# MCU_64.net
KiCad netlist of a schematic drawn in Altium Designer
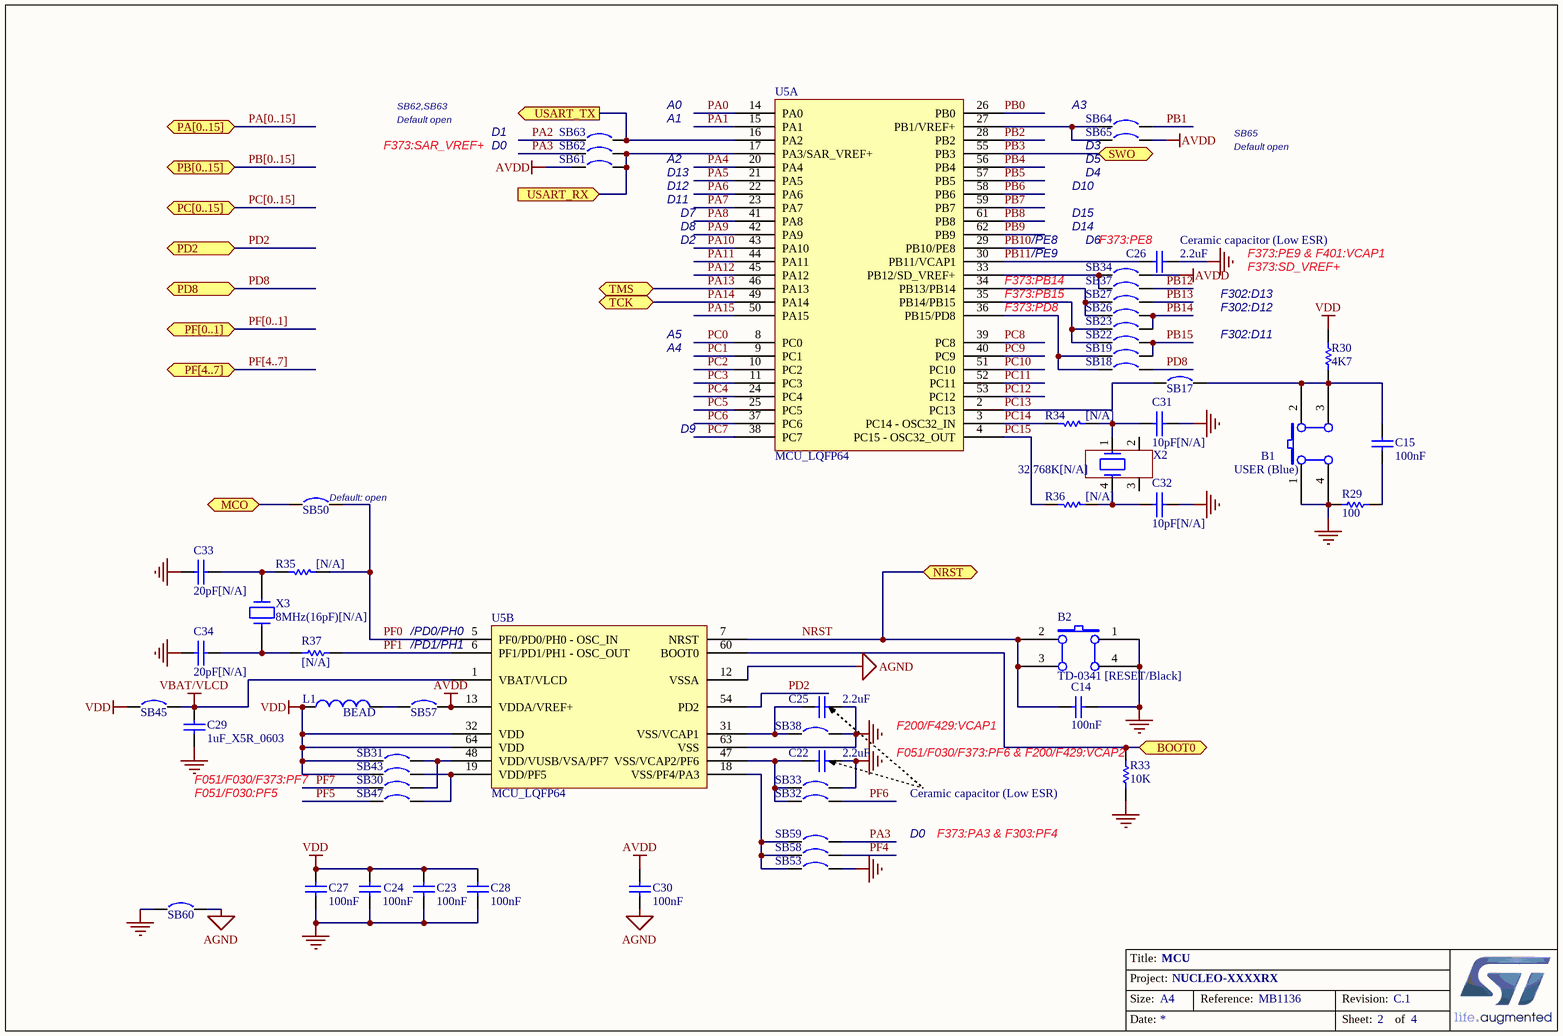
[diagram p0: MCU_64.SchDoc]

(export (version "E")
  (design (tool "Eeschema 10.0.6"))
  (components
    (comp (ref "B1")
      (value "USER (Blue)")
      (footprint "PB10")
      (description "SE PUSHBUTTON")
      (libsource (lib "Documents") (part "SW PUSHBUTTON"))
    )
    (comp (ref "B2")
      (value "TD-0341 [RESET/Black]")
      (footprint "PB10")
      (description "SE PUSHBUTTON")
      (libsource (lib "Documents") (part "SW PUSHBUTTON"))
    )
    (comp (ref "C14")
      (value "100nF")
      (footprint "0603C")
      (description "Capacitor")
      (fields (field (name "PUBLISHER") "Altium Limited"))
      (libsource (lib "Miscellaneous Devices") (part "CAP"))
    )
    (comp (ref "C15")
      (value "100nF")
      (footprint "0603C")
      (description "Capacitor")
      (fields (field (name "PUBLISHER") "Altium Limited"))
      (libsource (lib "Miscellaneous Devices") (part "CAP"))
    )
    (comp (ref "C22")
      (value "2.2uF")
      (footprint "TAN-A")
      (description "Capacitor,2.2uF,16V, X7R,10%,0805,YAGEO")
      (libsource (lib "MCD_TOOLS") (part "Cap_2.2uF_X7R_10%_0805"))
    )
    (comp (ref "C23")
      (value "100nF")
      (footprint "0603C")
      (description "Capacitor")
      (fields (field (name "PUBLISHER") "Altium Limited"))
      (libsource (lib "Miscellaneous Devices") (part "Cap"))
    )
    (comp (ref "C24")
      (value "100nF")
      (footprint "0603C")
      (description "Capacitor")
      (fields (field (name "PUBLISHER") "Altium Limited"))
      (libsource (lib "Miscellaneous Devices") (part "Cap"))
    )
    (comp (ref "C25")
      (value "2.2uF")
      (footprint "TAN-A")
      (description "Capacitor,2.2uF,16V, X7R,10%,0805,YAGEO")
      (libsource (lib "MCD_TOOLS") (part "Cap_2.2uF_X7R_10%_0805"))
    )
    (comp (ref "C26")
      (value "2.2uF")
      (footprint "TAN-A")
      (description "Capacitor,2.2uF,16V, X7R,10%,0805,YAGEO")
      (libsource (lib "MCD_TOOLS") (part "Cap_2.2uF_X7R_10%_0805"))
    )
    (comp (ref "C27")
      (value "100nF")
      (footprint "0603C")
      (description "Capacitor")
      (fields (field (name "PUBLISHER") "Altium Limited"))
      (libsource (lib "Miscellaneous Devices") (part "Cap"))
    )
    (comp (ref "C28")
      (value "100nF")
      (footprint "0603C")
      (description "Capacitor")
      (fields (field (name "PUBLISHER") "Altium Limited"))
      (libsource (lib "Miscellaneous Devices") (part "Cap"))
    )
    (comp (ref "C29")
      (value "1uF_X5R_0603")
      (footprint "0603C")
      (description "0603  X5R 1µF")
      (fields (field (name "TOLERANCE") "10%"))
      (libsource (lib "MB963_1") (part "CAP SMD 0603  X5R 1µF 25V 10%"))
    )
    (comp (ref "C30")
      (value "100nF")
      (footprint "0603C")
      (description "Capacitor")
      (fields (field (name "PUBLISHER") "Altium Limited"))
      (libsource (lib "Miscellaneous Devices") (part "Cap"))
    )
    (comp (ref "C31")
      (value "10pF[N/A]")
      (footprint "0603C")
      (description "Capacitor")
      (libsource (lib "") (part "CAP_1"))
    )
    (comp (ref "C32")
      (value "10pF[N/A]")
      (footprint "0603C")
      (description "Capacitor")
      (libsource (lib "") (part "CAP_1"))
    )
    (comp (ref "C33")
      (value "20pF[N/A]")
      (footprint "0603C")
      (description "Capacitor")
      (libsource (lib "*") (part "CAP"))
    )
    (comp (ref "C34")
      (value "20pF[N/A]")
      (footprint "0603C")
      (description "Capacitor")
      (libsource (lib "*") (part "CAP"))
    )
    (comp (ref "L1")
      (value "BEAD")
      (footprint "0603L")
      (description "Inductor")
      (fields (field (name "PUBLISHER") "Altium Limited"))
      (libsource (lib "Miscellaneous Devices") (part "Inductor"))
    )
    (comp (ref "R29")
      (value "100")
      (footprint "0603R")
      (description "Resistor")
      (fields (field (name "PUBLISHER") "Altium Limited"))
      (libsource (lib "Miscellaneous Devices") (part "Res1"))
    )
    (comp (ref "R30")
      (value "4K7")
      (footprint "0603R")
      (description "Resistor")
      (fields (field (name "PUBLISHER") "Altium Limited"))
      (libsource (lib "Miscellaneous Devices") (part "res1"))
    )
    (comp (ref "R33")
      (value "10K")
      (footprint "0603R")
      (description "Resistor")
      (fields (field (name "PUBLISHER") "Altium Limited"))
      (libsource (lib "Miscellaneous Devices") (part "res1"))
    )
    (comp (ref "R34")
      (value "[N/A]")
      (footprint "0603R")
      (description "Resistor")
      (fields (field (name "PUBLISHER") "Altium Limited"))
      (libsource (lib "") (part "Res1_1"))
    )
    (comp (ref "R35")
      (value "[N/A]")
      (footprint "0603R")
      (description "Resistor")
      (fields (field (name "PUBLISHER") "Altium Limited"))
      (libsource (lib "") (part "Res1_1"))
    )
    (comp (ref "R36")
      (value "[N/A]")
      (footprint "0603R")
      (description "Resistor")
      (fields (field (name "PUBLISHER") "Altium Limited"))
      (libsource (lib "") (part "Res1_1"))
    )
    (comp (ref "R37")
      (value "[N/A]")
      (footprint "0603R")
      (description "Resistor")
      (fields (field (name "PUBLISHER") "Altium Limited"))
      (libsource (lib "Miscellaneous Devices") (part "Res1"))
    )
    (comp (ref "SB17")
      (value "Circuit Breaker")
      (footprint "JP2_SMD")
      (fields (field (name "PUBLISHER") "Altium Limited"))
      (libsource (lib "MCD_TOOLS") (part "Circuit Breaker"))
    )
    (comp (ref "SB18")
      (value "Circuit Breaker")
      (footprint "JP2_SMD")
      (fields (field (name "PUBLISHER") "Altium Limited"))
      (libsource (lib "MCD_TOOLS") (part "Circuit Breaker"))
    )
    (comp (ref "SB19")
      (value "Circuit Breaker")
      (footprint "JP2_SMD")
      (fields (field (name "PUBLISHER") "Altium Limited"))
      (libsource (lib "MCD_TOOLS") (part "Circuit Breaker"))
    )
    (comp (ref "SB22")
      (value "Circuit Breaker")
      (footprint "JP2_SMD")
      (fields (field (name "PUBLISHER") "Altium Limited"))
      (libsource (lib "MCD_TOOLS") (part "Circuit Breaker"))
    )
    (comp (ref "SB23")
      (value "Circuit Breaker")
      (footprint "JP2_SMD")
      (fields (field (name "PUBLISHER") "Altium Limited"))
      (libsource (lib "MCD_TOOLS") (part "Circuit Breaker"))
    )
    (comp (ref "SB26")
      (value "Circuit Breaker")
      (footprint "JP2_SMD")
      (fields (field (name "PUBLISHER") "Altium Limited"))
      (libsource (lib "MCD_TOOLS") (part "Circuit Breaker"))
    )
    (comp (ref "SB27")
      (value "Circuit Breaker")
      (footprint "JP2_SMD")
      (fields (field (name "PUBLISHER") "Altium Limited"))
      (libsource (lib "MCD_TOOLS") (part "Circuit Breaker"))
    )
    (comp (ref "SB30")
      (value "Circuit Breaker")
      (footprint "JP2_SMD")
      (fields (field (name "PUBLISHER") "Altium Limited"))
      (libsource (lib "MCD_TOOLS") (part "Circuit Breaker"))
    )
    (comp (ref "SB31")
      (value "Circuit Breaker")
      (footprint "JP2_SMD")
      (fields (field (name "PUBLISHER") "Altium Limited"))
      (libsource (lib "MCD_TOOLS") (part "Circuit Breaker"))
    )
    (comp (ref "SB32")
      (value "Circuit Breaker")
      (footprint "JP2_SMD")
      (fields (field (name "PUBLISHER") "Altium Limited"))
      (libsource (lib "MCD_TOOLS") (part "Circuit Breaker"))
    )
    (comp (ref "SB33")
      (value "Circuit Breaker")
      (footprint "JP2_SMD")
      (fields (field (name "PUBLISHER") "Altium Limited"))
      (libsource (lib "MCD_TOOLS") (part "Circuit Breaker"))
    )
    (comp (ref "SB34")
      (value "Circuit Breaker")
      (footprint "JP2_SMD")
      (fields (field (name "PUBLISHER") "Altium Limited"))
      (libsource (lib "MCD_TOOLS") (part "Circuit Breaker"))
    )
    (comp (ref "SB37")
      (value "Circuit Breaker")
      (footprint "JP2_SMD")
      (fields (field (name "PUBLISHER") "Altium Limited"))
      (libsource (lib "MCD_TOOLS") (part "Circuit Breaker"))
    )
    (comp (ref "SB38")
      (value "Circuit Breaker")
      (footprint "JP2_SMD")
      (fields (field (name "PUBLISHER") "Altium Limited"))
      (libsource (lib "MCD_TOOLS") (part "Circuit Breaker"))
    )
    (comp (ref "SB43")
      (value "Circuit Breaker")
      (footprint "JP2_SMD")
      (fields (field (name "PUBLISHER") "Altium Limited"))
      (libsource (lib "MCD_TOOLS") (part "Circuit Breaker"))
    )
    (comp (ref "SB45")
      (value "Circuit Breaker")
      (footprint "JP2_SMD")
      (fields (field (name "PUBLISHER") "Altium Limited"))
      (libsource (lib "MCD_TOOLS") (part "Circuit Breaker"))
    )
    (comp (ref "SB47")
      (value "Circuit Breaker")
      (footprint "JP2_SMD")
      (fields (field (name "PUBLISHER") "Altium Limited"))
      (libsource (lib "MCD_TOOLS") (part "Circuit Breaker"))
    )
    (comp (ref "SB50")
      (value "Circuit Breaker")
      (footprint "JP2_SMD")
      (fields (field (name "PUBLISHER") "Altium Limited"))
      (libsource (lib "MCD_TOOLS") (part "Circuit Breaker"))
    )
    (comp (ref "SB53")
      (value "Circuit Breaker")
      (footprint "JP2_SMD")
      (fields (field (name "PUBLISHER") "Altium Limited"))
      (libsource (lib "MCD_TOOLS") (part "Circuit Breaker"))
    )
    (comp (ref "SB57")
      (value "Circuit Breaker")
      (footprint "JP2_SMD")
      (fields (field (name "PUBLISHER") "Altium Limited"))
      (libsource (lib "MCD_TOOLS") (part "Circuit Breaker"))
    )
    (comp (ref "SB58")
      (value "Circuit Breaker")
      (footprint "JP2_SMD")
      (fields (field (name "PUBLISHER") "Altium Limited"))
      (libsource (lib "MCD_TOOLS") (part "Circuit Breaker"))
    )
    (comp (ref "SB59")
      (value "Circuit Breaker")
      (footprint "JP2_SMD")
      (fields (field (name "PUBLISHER") "Altium Limited"))
      (libsource (lib "MCD_TOOLS") (part "Circuit Breaker"))
    )
    (comp (ref "SB60")
      (value "Circuit Breaker")
      (footprint "JP2_SMD")
      (fields (field (name "PUBLISHER") "Altium Limited"))
      (libsource (lib "MCD_TOOLS") (part "Circuit Breaker"))
    )
    (comp (ref "SB61")
      (value "Circuit Breaker")
      (footprint "JP2_SMD")
      (fields (field (name "PUBLISHER") "Altium Limited"))
      (libsource (lib "MCD_TOOLS") (part "Circuit Breaker"))
    )
    (comp (ref "SB62")
      (value "Circuit Breaker")
      (footprint "JP2_SMD")
      (fields (field (name "PUBLISHER") "Altium Limited"))
      (libsource (lib "MCD_TOOLS") (part "Circuit Breaker"))
    )
    (comp (ref "SB63")
      (value "Circuit Breaker")
      (footprint "JP2_SMD")
      (fields (field (name "PUBLISHER") "Altium Limited"))
      (libsource (lib "MCD_TOOLS") (part "Circuit Breaker"))
    )
    (comp (ref "SB64")
      (value "Circuit Breaker")
      (footprint "JP2_SMD")
      (fields (field (name "PUBLISHER") "Altium Limited"))
      (libsource (lib "MCD_TOOLS") (part "Circuit Breaker"))
    )
    (comp (ref "SB65")
      (value "Circuit Breaker")
      (footprint "JP2_SMD")
      (fields (field (name "PUBLISHER") "Altium Limited"))
      (libsource (lib "MCD_TOOLS") (part "Circuit Breaker"))
    )
    (comp (ref "U5")
      (value "MCU_LQFP64")
      (footprint "LQFP64")
      (libsource (lib "Nucleo_64") (part "MCU_LQFP64"))
    )
    (comp (ref "X2") (value "32.768K[N/A]") (footprint "XTAL_4SM_8X3R8") (libsource (lib "*") (part "MC306")))
    (comp (ref "X3")
      (value "8MHz(16pF)[N/A]")
      (footprint "XTAL1")
      (description "Crystal")
      (libsource (lib "*") (part "CRYSTAL"))
    )
  )
  (nets
    (net (code "1") (name "/BOOT0") (class "Default")
      (node (ref "R33") (pin "1") (pinfunction "1_1") (pintype "passive"))
      (node (ref "U5") (pin "60") (pinfunction "BOOT0_60") (pintype "passive"))
    )
    (net (code "2") (name "/MCO") (class "Default")
      (node (ref "SB50") (pin "1") (pinfunction "1_1") (pintype "passive"))
    )
    (net (code "3") (name "/NRST") (class "Default")
      (node (ref "B2") (pin "2") (pinfunction "B0_2") (pintype "passive"))
      (node (ref "B2") (pin "3") (pinfunction "B1_3") (pintype "passive"))
      (node (ref "C14") (pin "2") (pinfunction "2_2") (pintype "passive"))
      (node (ref "U5") (pin "7") (pinfunction "NRST_7") (pintype "passive"))
    )
    (net (code "4") (name "/PA0") (class "Default")
      (node (ref "U5") (pin "14") (pinfunction "PA0_14") (pintype "passive"))
    )
    (net (code "5") (name "/PA1") (class "Default")
      (node (ref "U5") (pin "15") (pinfunction "PA1_15") (pintype "passive"))
    )
    (net (code "6") (name "/PA2") (class "Default")
      (node (ref "SB63") (pin "1") (pinfunction "1_1") (pintype "passive"))
    )
    (net (code "7") (name "/PA3") (class "Default")
      (node (ref "SB59") (pin "2") (pinfunction "2_2") (pintype "passive"))
      (node (ref "SB62") (pin "1") (pinfunction "1_1") (pintype "passive"))
    )
    (net (code "8") (name "/PA4") (class "Default")
      (node (ref "U5") (pin "20") (pinfunction "PA4_20") (pintype "passive"))
    )
    (net (code "9") (name "/PA5") (class "Default")
      (node (ref "U5") (pin "21") (pinfunction "PA5_21") (pintype "passive"))
    )
    (net (code "10") (name "/PA6") (class "Default")
      (node (ref "U5") (pin "22") (pinfunction "PA6_22") (pintype "passive"))
    )
    (net (code "11") (name "/PA7") (class "Default")
      (node (ref "U5") (pin "23") (pinfunction "PA7_23") (pintype "passive"))
    )
    (net (code "12") (name "/PA8") (class "Default")
      (node (ref "U5") (pin "41") (pinfunction "PA8_41") (pintype "passive"))
    )
    (net (code "13") (name "/PA9") (class "Default")
      (node (ref "U5") (pin "42") (pinfunction "PA9_42") (pintype "passive"))
    )
    (net (code "14") (name "/PA10") (class "Default")
      (node (ref "U5") (pin "43") (pinfunction "PA10_43") (pintype "passive"))
    )
    (net (code "15") (name "/PA11") (class "Default")
      (node (ref "U5") (pin "44") (pinfunction "PA11_44") (pintype "passive"))
    )
    (net (code "16") (name "/PA12") (class "Default")
      (node (ref "U5") (pin "45") (pinfunction "PA12_45") (pintype "passive"))
    )
    (net (code "17") (name "/PA13") (class "Default")
      (node (ref "U5") (pin "46") (pinfunction "PA13_46") (pintype "passive"))
    )
    (net (code "18") (name "/PA14") (class "Default")
      (node (ref "U5") (pin "49") (pinfunction "PA14_49") (pintype "passive"))
    )
    (net (code "19") (name "/PA15") (class "Default")
      (node (ref "U5") (pin "50") (pinfunction "PA15_50") (pintype "passive"))
    )
    (net (code "21") (name "/PB0") (class "Default")
      (node (ref "U5") (pin "26") (pinfunction "PB0_26") (pintype "passive"))
    )
    (net (code "22") (name "/PB1") (class "Default")
      (node (ref "SB64") (pin "2") (pinfunction "2_2") (pintype "passive"))
    )
    (net (code "23") (name "/PB2") (class "Default")
      (node (ref "U5") (pin "28") (pinfunction "PB2_28") (pintype "passive"))
    )
    (net (code "24") (name "/PB3") (class "Default")
      (node (ref "U5") (pin "55") (pinfunction "PB3_55") (pintype "passive"))
    )
    (net (code "25") (name "/PB4") (class "Default")
      (node (ref "U5") (pin "56") (pinfunction "PB4_56") (pintype "passive"))
    )
    (net (code "26") (name "/PB5") (class "Default")
      (node (ref "U5") (pin "57") (pinfunction "PB5_57") (pintype "passive"))
    )
    (net (code "27") (name "/PB6") (class "Default")
      (node (ref "U5") (pin "58") (pinfunction "PB6_58") (pintype "passive"))
    )
    (net (code "28") (name "/PB7") (class "Default")
      (node (ref "U5") (pin "59") (pinfunction "PB7_59") (pintype "passive"))
    )
    (net (code "29") (name "/PB8") (class "Default")
      (node (ref "U5") (pin "61") (pinfunction "PB8_61") (pintype "passive"))
    )
    (net (code "30") (name "/PB9") (class "Default")
      (node (ref "U5") (pin "62") (pinfunction "PB9_62") (pintype "passive"))
    )
    (net (code "31") (name "/PB10") (class "Default")
      (node (ref "U5") (pin "29") (pinfunction "PB10/PE8_29") (pintype "passive"))
    )
    (net (code "32") (name "/PB11") (class "Default")
      (node (ref "C26") (pin "1") (pinfunction "1_1") (pintype "passive"))
      (node (ref "U5") (pin "30") (pinfunction "PB11/VCAP1_30") (pintype "passive"))
    )
    (net (code "33") (name "/PB12") (class "Default")
      (node (ref "SB37") (pin "2") (pinfunction "2_2") (pintype "passive"))
    )
    (net (code "34") (name "/PB13") (class "Default")
      (node (ref "SB27") (pin "2") (pinfunction "2_2") (pintype "passive"))
    )
    (net (code "35") (name "/PB14") (class "Default")
      (node (ref "SB23") (pin "2") (pinfunction "2_2") (pintype "passive"))
      (node (ref "SB26") (pin "2") (pinfunction "2_2") (pintype "passive"))
    )
    (net (code "36") (name "/PB15") (class "Default")
      (node (ref "SB19") (pin "2") (pinfunction "2_2") (pintype "passive"))
      (node (ref "SB22") (pin "2") (pinfunction "2_2") (pintype "passive"))
    )
    (net (code "38") (name "/PC0") (class "Default")
      (node (ref "U5") (pin "8") (pinfunction "PC0_8") (pintype "passive"))
    )
    (net (code "39") (name "/PC1") (class "Default")
      (node (ref "U5") (pin "9") (pinfunction "PC1_9") (pintype "passive"))
    )
    (net (code "40") (name "/PC2") (class "Default")
      (node (ref "U5") (pin "10") (pinfunction "PC2_10") (pintype "passive"))
    )
    (net (code "41") (name "/PC3") (class "Default")
      (node (ref "U5") (pin "11") (pinfunction "PC3_11") (pintype "passive"))
    )
    (net (code "42") (name "/PC4") (class "Default")
      (node (ref "U5") (pin "24") (pinfunction "PC4_24") (pintype "passive"))
    )
    (net (code "43") (name "/PC5") (class "Default")
      (node (ref "U5") (pin "25") (pinfunction "PC5_25") (pintype "passive"))
    )
    (net (code "44") (name "/PC6") (class "Default")
      (node (ref "U5") (pin "37") (pinfunction "PC6_37") (pintype "passive"))
    )
    (net (code "45") (name "/PC7") (class "Default")
      (node (ref "U5") (pin "38") (pinfunction "PC7_38") (pintype "passive"))
    )
    (net (code "46") (name "/PC8") (class "Default")
      (node (ref "U5") (pin "39") (pinfunction "PC8_39") (pintype "passive"))
    )
    (net (code "47") (name "/PC9") (class "Default")
      (node (ref "U5") (pin "40") (pinfunction "PC9_40") (pintype "passive"))
    )
    (net (code "48") (name "/PC10") (class "Default")
      (node (ref "U5") (pin "51") (pinfunction "PC10_51") (pintype "passive"))
    )
    (net (code "49") (name "/PC11") (class "Default")
      (node (ref "U5") (pin "52") (pinfunction "PC11_52") (pintype "passive"))
    )
    (net (code "50") (name "/PC12") (class "Default")
      (node (ref "U5") (pin "53") (pinfunction "PC12_53") (pintype "passive"))
    )
    (net (code "51") (name "/PC13") (class "Default")
      (node (ref "SB17") (pin "1") (pinfunction "1_1") (pintype "passive"))
      (node (ref "U5") (pin "2") (pinfunction "PC13_2") (pintype "passive"))
    )
    (net (code "52") (name "/PC14") (class "Default")
      (node (ref "R34") (pin "2") (pinfunction "2_2") (pintype "passive"))
      (node (ref "U5") (pin "3") (pinfunction "PC14_-_OSC32_IN_3") (pintype "passive"))
    )
    (net (code "53") (name "/PC15") (class "Default")
      (node (ref "R36") (pin "2") (pinfunction "2_2") (pintype "passive"))
      (node (ref "U5") (pin "4") (pinfunction "PC15_-_OSC32_OUT_4") (pintype "passive"))
    )
    (net (code "55") (name "/PD2") (class "Default")
      (node (ref "U5") (pin "54") (pinfunction "PD2_54") (pintype "passive"))
    )
    (net (code "56") (name "/PD8") (class "Default")
      (node (ref "SB18") (pin "2") (pinfunction "2_2") (pintype "passive"))
    )
    (net (code "57") (name "/PF0") (class "Default")
      (node (ref "R35") (pin "1") (pinfunction "1_1") (pintype "passive"))
      (node (ref "SB50") (pin "2") (pinfunction "2_2") (pintype "passive"))
      (node (ref "U5") (pin "5") (pinfunction "PF0/PD0/PH0_-_OSC_IN_5") (pintype "passive"))
    )
    (net (code "58") (name "/PF1") (class "Default")
      (node (ref "R37") (pin "1") (pinfunction "1_1") (pintype "passive"))
      (node (ref "U5") (pin "6") (pinfunction "PF1/PD1/PH1_-_OSC_OUT_6") (pintype "passive"))
    )
    (net (code "59") (name "/PF4") (class "Default")
      (node (ref "SB58") (pin "2") (pinfunction "2_2") (pintype "passive"))
    )
    (net (code "60") (name "/PF5") (class "Default")
      (node (ref "SB47") (pin "1") (pinfunction "1_1") (pintype "passive"))
    )
    (net (code "61") (name "/PF6") (class "Default")
      (node (ref "SB32") (pin "2") (pinfunction "2_2") (pintype "passive"))
    )
    (net (code "62") (name "/PF7") (class "Default")
      (node (ref "SB30") (pin "1") (pinfunction "1_1") (pintype "passive"))
    )
    (net (code "65") (name "/USART_RX") (class "Default")
      (node (ref "SB61") (pin "2") (pinfunction "2_2") (pintype "passive"))
      (node (ref "SB62") (pin "2") (pinfunction "2_2") (pintype "passive"))
      (node (ref "U5") (pin "17") (pinfunction "PA3/SAR_VREF+_17") (pintype "passive"))
    )
    (net (code "66") (name "/USART_TX") (class "Default")
      (node (ref "SB63") (pin "2") (pinfunction "2_2") (pintype "passive"))
      (node (ref "U5") (pin "16") (pinfunction "PA2_16") (pintype "passive"))
    )
    (net (code "67") (name "AGND") (class "Default")
      (node (ref "C30") (pin "2") (pinfunction "2_2") (pintype "passive"))
      (node (ref "SB60") (pin "2") (pinfunction "2_2") (pintype "passive"))
      (node (ref "U5") (pin "12") (pinfunction "VSSA_12") (pintype "passive"))
    )
    (net (code "68") (name "AVDD") (class "Default")
      (node (ref "C30") (pin "1") (pinfunction "1_1") (pintype "passive"))
      (node (ref "SB34") (pin "2") (pinfunction "2_2") (pintype "passive"))
      (node (ref "SB57") (pin "2") (pinfunction "2_2") (pintype "passive"))
      (node (ref "SB61") (pin "1") (pinfunction "1_1") (pintype "passive"))
      (node (ref "SB65") (pin "2") (pinfunction "2_2") (pintype "passive"))
      (node (ref "U5") (pin "13") (pinfunction "VDDA/VREF+_13") (pintype "passive"))
    )
    (net (code "69") (name "GND") (class "Default")
      (node (ref "B1") (pin "1") (pinfunction "A0_1") (pintype "passive"))
      (node (ref "B1") (pin "4") (pinfunction "A1_4") (pintype "passive"))
      (node (ref "B2") (pin "1") (pinfunction "A0_1") (pintype "passive"))
      (node (ref "B2") (pin "4") (pinfunction "A1_4") (pintype "passive"))
      (node (ref "C14") (pin "1") (pinfunction "1_1") (pintype "passive"))
      (node (ref "C22") (pin "2") (pinfunction "2_2") (pintype "passive"))
      (node (ref "C23") (pin "2") (pinfunction "2_2") (pintype "passive"))
      (node (ref "C24") (pin "2") (pinfunction "2_2") (pintype "passive"))
      (node (ref "C25") (pin "2") (pinfunction "2_2") (pintype "passive"))
      (node (ref "C26") (pin "2") (pinfunction "2_2") (pintype "passive"))
      (node (ref "C27") (pin "2") (pinfunction "2_2") (pintype "passive"))
      (node (ref "C28") (pin "2") (pinfunction "2_2") (pintype "passive"))
      (node (ref "C29") (pin "2") (pinfunction "2_2") (pintype "passive"))
      (node (ref "C31") (pin "2") (pinfunction "2_2") (pintype "passive"))
      (node (ref "C32") (pin "2") (pinfunction "2_2") (pintype "passive"))
      (node (ref "C33") (pin "2") (pinfunction "2_2") (pintype "passive"))
      (node (ref "C34") (pin "2") (pinfunction "2_2") (pintype "passive"))
      (node (ref "R29") (pin "1") (pinfunction "1_1") (pintype "passive"))
      (node (ref "R33") (pin "2") (pinfunction "2_2") (pintype "passive"))
      (node (ref "SB33") (pin "2") (pinfunction "2_2") (pintype "passive"))
      (node (ref "SB38") (pin "2") (pinfunction "2_2") (pintype "passive"))
      (node (ref "SB53") (pin "2") (pinfunction "2_2") (pintype "passive"))
      (node (ref "SB60") (pin "1") (pinfunction "1_1") (pintype "passive"))
      (node (ref "U5") (pin "63") (pinfunction "VSS_63") (pintype "passive"))
    )
    (net (code "70") (name "Net-(B1-B0)") (class "Default")
      (node (ref "B1") (pin "2") (pinfunction "B0_2") (pintype "passive"))
      (node (ref "B1") (pin "3") (pinfunction "B1_3") (pintype "passive"))
      (node (ref "C15") (pin "2") (pinfunction "2_2") (pintype "passive"))
      (node (ref "R30") (pin "1") (pinfunction "1_1") (pintype "passive"))
      (node (ref "SB17") (pin "2") (pinfunction "2_2") (pintype "passive"))
    )
    (net (code "71") (name "Net-(C15-Pad1)") (class "Default")
      (node (ref "C15") (pin "1") (pinfunction "1_1") (pintype "passive"))
      (node (ref "R29") (pin "2") (pinfunction "2_2") (pintype "passive"))
    )
    (net (code "72") (name "Net-(C31-Pad1)") (class "Default")
      (node (ref "C31") (pin "1") (pinfunction "1_1") (pintype "passive"))
      (node (ref "R34") (pin "1") (pinfunction "1_1") (pintype "passive"))
      (node (ref "X2") (pin "1") (pinfunction "1_1") (pintype "passive"))
    )
    (net (code "73") (name "Net-(C32-Pad1)") (class "Default")
      (node (ref "C32") (pin "1") (pinfunction "1_1") (pintype "passive"))
      (node (ref "R36") (pin "1") (pinfunction "1_1") (pintype "passive"))
      (node (ref "X2") (pin "4") (pinfunction "4_4") (pintype "passive"))
    )
    (net (code "74") (name "Net-(C33-Pad1)") (class "Default")
      (node (ref "C33") (pin "1") (pinfunction "1_1") (pintype "passive"))
      (node (ref "R35") (pin "2") (pinfunction "2_2") (pintype "passive"))
      (node (ref "X3") (pin "2") (pinfunction "2_2") (pintype "passive"))
    )
    (net (code "75") (name "Net-(C34-Pad1)") (class "Default")
      (node (ref "C34") (pin "1") (pinfunction "1_1") (pintype "passive"))
      (node (ref "R37") (pin "2") (pinfunction "2_2") (pintype "passive"))
      (node (ref "X3") (pin "1") (pinfunction "1_1") (pintype "passive"))
    )
    (net (code "76") (name "Net-(L1-Pad2)") (class "Default")
      (node (ref "L1") (pin "2") (pinfunction "2_2") (pintype "passive"))
      (node (ref "SB57") (pin "1") (pinfunction "1_1") (pintype "passive"))
    )
    (net (code "77") (name "Net-(U5A-PB1{slash}VREF+)") (class "Default")
      (node (ref "SB64") (pin "1") (pinfunction "1_1") (pintype "passive"))
      (node (ref "SB65") (pin "1") (pinfunction "1_1") (pintype "passive"))
      (node (ref "U5") (pin "27") (pinfunction "PB1/VREF+_27") (pintype "passive"))
    )
    (net (code "78") (name "Net-(U5A-PB12{slash}SD_VREF+)") (class "Default")
      (node (ref "SB34") (pin "1") (pinfunction "1_1") (pintype "passive"))
      (node (ref "SB37") (pin "1") (pinfunction "1_1") (pintype "passive"))
      (node (ref "U5") (pin "33") (pinfunction "PB12/SD_VREF+_33") (pintype "passive"))
    )
    (net (code "79") (name "Net-(U5A-PB13{slash}PB14)") (class "Default")
      (node (ref "SB26") (pin "1") (pinfunction "1_1") (pintype "passive"))
      (node (ref "SB27") (pin "1") (pinfunction "1_1") (pintype "passive"))
      (node (ref "U5") (pin "34") (pinfunction "PB13/PB14_34") (pintype "passive"))
    )
    (net (code "80") (name "Net-(U5A-PB14{slash}PB15)") (class "Default")
      (node (ref "SB22") (pin "1") (pinfunction "1_1") (pintype "passive"))
      (node (ref "SB23") (pin "1") (pinfunction "1_1") (pintype "passive"))
      (node (ref "U5") (pin "35") (pinfunction "PB14/PB15_35") (pintype "passive"))
    )
    (net (code "81") (name "Net-(U5A-PB15{slash}PD8)") (class "Default")
      (node (ref "SB18") (pin "1") (pinfunction "1_1") (pintype "passive"))
      (node (ref "SB19") (pin "1") (pinfunction "1_1") (pintype "passive"))
      (node (ref "U5") (pin "36") (pinfunction "PB15/PD8_36") (pintype "passive"))
    )
    (net (code "82") (name "Net-(U5B-VDD{slash}PF5)") (class "Default")
      (node (ref "SB43") (pin "2") (pinfunction "2_2") (pintype "passive"))
      (node (ref "SB47") (pin "2") (pinfunction "2_2") (pintype "passive"))
      (node (ref "U5") (pin "19") (pinfunction "VDD/PF5_19") (pintype "passive"))
    )
    (net (code "83") (name "Net-(U5B-VDD{slash}VUSB{slash}VSA{slash}PF7)") (class "Default")
      (node (ref "SB30") (pin "2") (pinfunction "2_2") (pintype "passive"))
      (node (ref "SB31") (pin "2") (pinfunction "2_2") (pintype "passive"))
      (node (ref "U5") (pin "48") (pinfunction "VDD/VUSB/VSA/PF7_48") (pintype "passive"))
    )
    (net (code "84") (name "Net-(U5B-VSS{slash}PF4{slash}PA3)") (class "Default")
      (node (ref "SB53") (pin "1") (pinfunction "1_1") (pintype "passive"))
      (node (ref "SB58") (pin "1") (pinfunction "1_1") (pintype "passive"))
      (node (ref "SB59") (pin "1") (pinfunction "1_1") (pintype "passive"))
      (node (ref "U5") (pin "18") (pinfunction "VSS/PF4/PA3_18") (pintype "passive"))
    )
    (net (code "85") (name "Net-(U5B-VSS{slash}VCAP1)") (class "Default")
      (node (ref "C25") (pin "1") (pinfunction "1_1") (pintype "passive"))
      (node (ref "SB38") (pin "1") (pinfunction "1_1") (pintype "passive"))
      (node (ref "U5") (pin "31") (pinfunction "VSS/VCAP1_31") (pintype "passive"))
    )
    (net (code "86") (name "Net-(U5B-VSS{slash}VCAP2{slash}PF6)") (class "Default")
      (node (ref "C22") (pin "1") (pinfunction "1_1") (pintype "passive"))
      (node (ref "SB32") (pin "1") (pinfunction "1_1") (pintype "passive"))
      (node (ref "SB33") (pin "1") (pinfunction "1_1") (pintype "passive"))
      (node (ref "U5") (pin "47") (pinfunction "VSS/VCAP2/PF6_47") (pintype "passive"))
    )
    (net (code "87") (name "VBAT{slash}VLCD") (class "Default")
      (node (ref "C29") (pin "1") (pinfunction "1_1") (pintype "passive"))
      (node (ref "SB45") (pin "2") (pinfunction "2_2") (pintype "passive"))
      (node (ref "U5") (pin "1") (pinfunction "VBAT/VLCD_1") (pintype "passive"))
    )
    (net (code "88") (name "VDD") (class "Default")
      (node (ref "C23") (pin "1") (pinfunction "1_1") (pintype "passive"))
      (node (ref "C24") (pin "1") (pinfunction "1_1") (pintype "passive"))
      (node (ref "C27") (pin "1") (pinfunction "1_1") (pintype "passive"))
      (node (ref "C28") (pin "1") (pinfunction "1_1") (pintype "passive"))
      (node (ref "L1") (pin "1") (pinfunction "1_1") (pintype "passive"))
      (node (ref "R30") (pin "2") (pinfunction "2_2") (pintype "passive"))
      (node (ref "SB31") (pin "1") (pinfunction "1_1") (pintype "passive"))
      (node (ref "SB43") (pin "1") (pinfunction "1_1") (pintype "passive"))
      (node (ref "SB45") (pin "1") (pinfunction "1_1") (pintype "passive"))
      (node (ref "U5") (pin "32") (pinfunction "VDD_32") (pintype "passive"))
      (node (ref "U5") (pin "64") (pinfunction "VDD_64") (pintype "passive"))
    )
    (net (code "89") (name "unconnected-(X2-Pad2)") (class "Default")
      (node (ref "X2") (pin "2") (pinfunction "2_2") (pintype "passive"))
    )
    (net (code "90") (name "unconnected-(X2-Pad3)") (class "Default")
      (node (ref "X2") (pin "3") (pinfunction "3_3") (pintype "passive"))
    )
  )
)
